# v7_mainboard_rpizerow.net
KiCad netlist of a schematic drawn in EAGLE
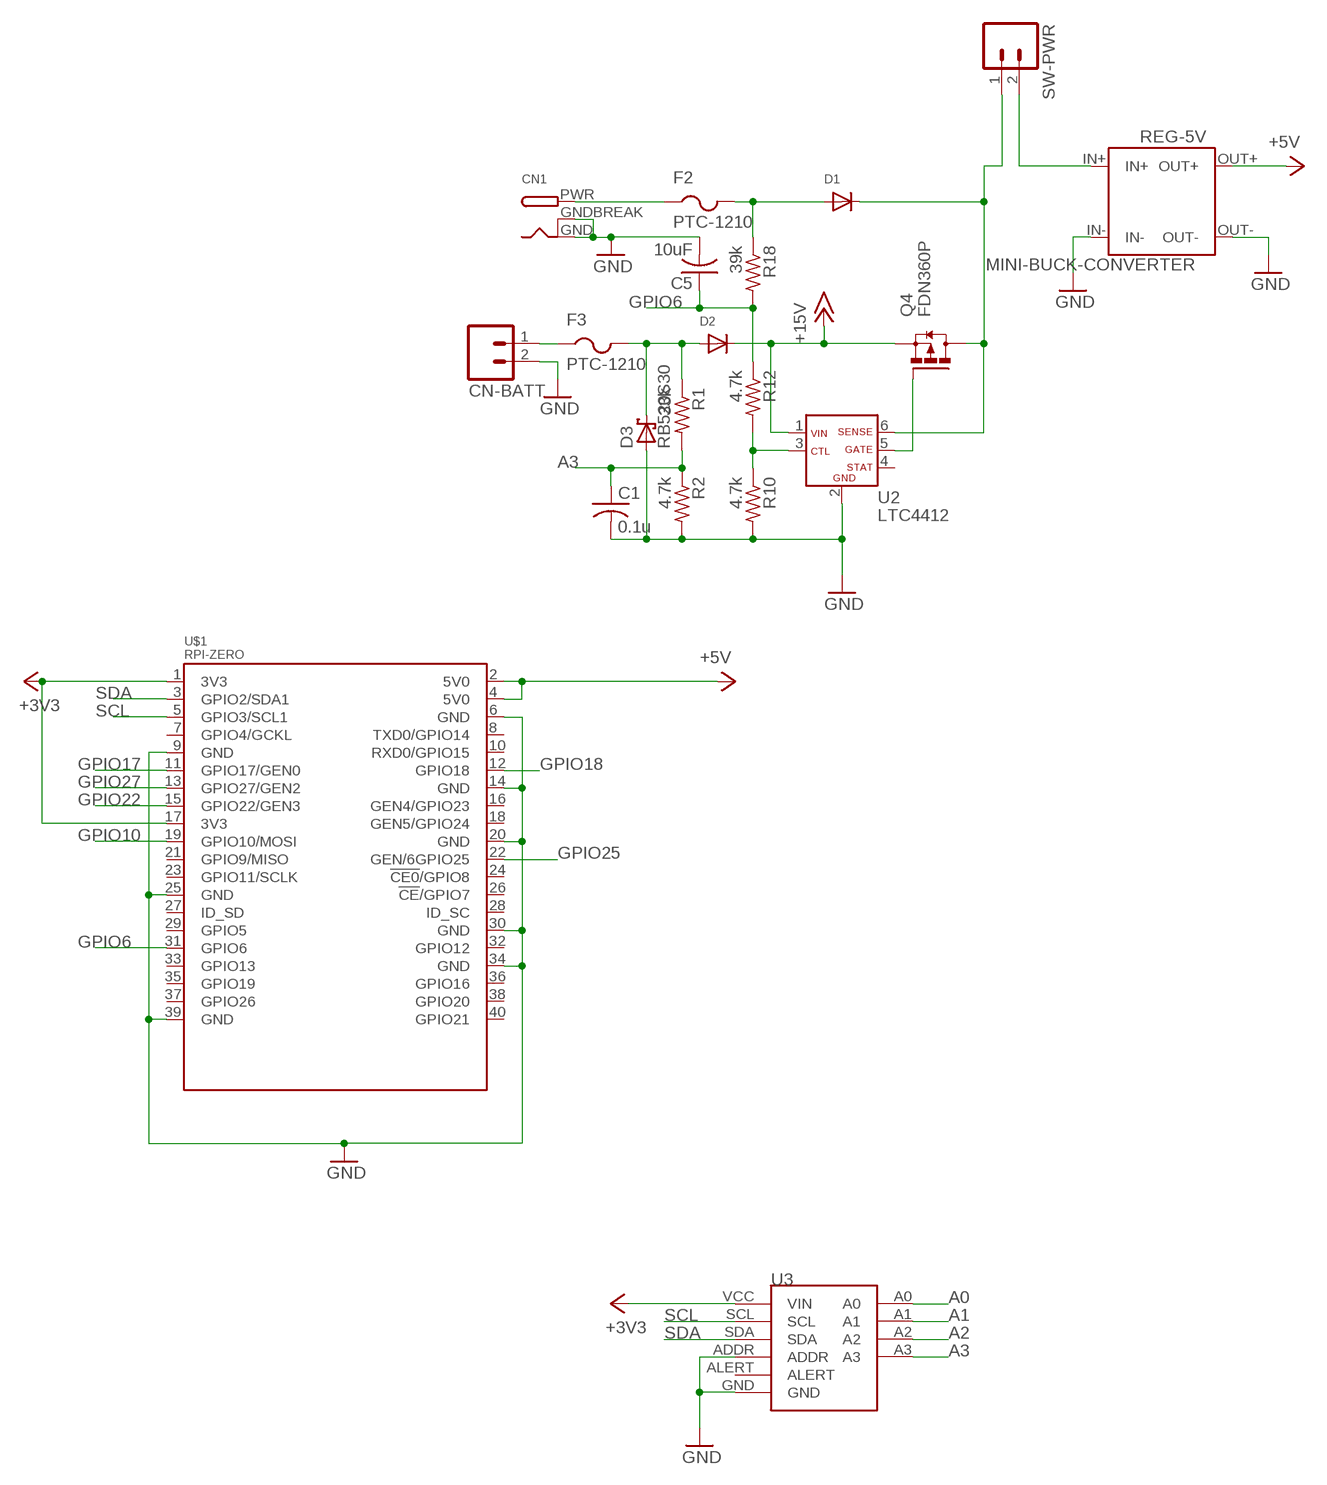
[diagram p0: schematic, sheet 1, part 1 of 2]
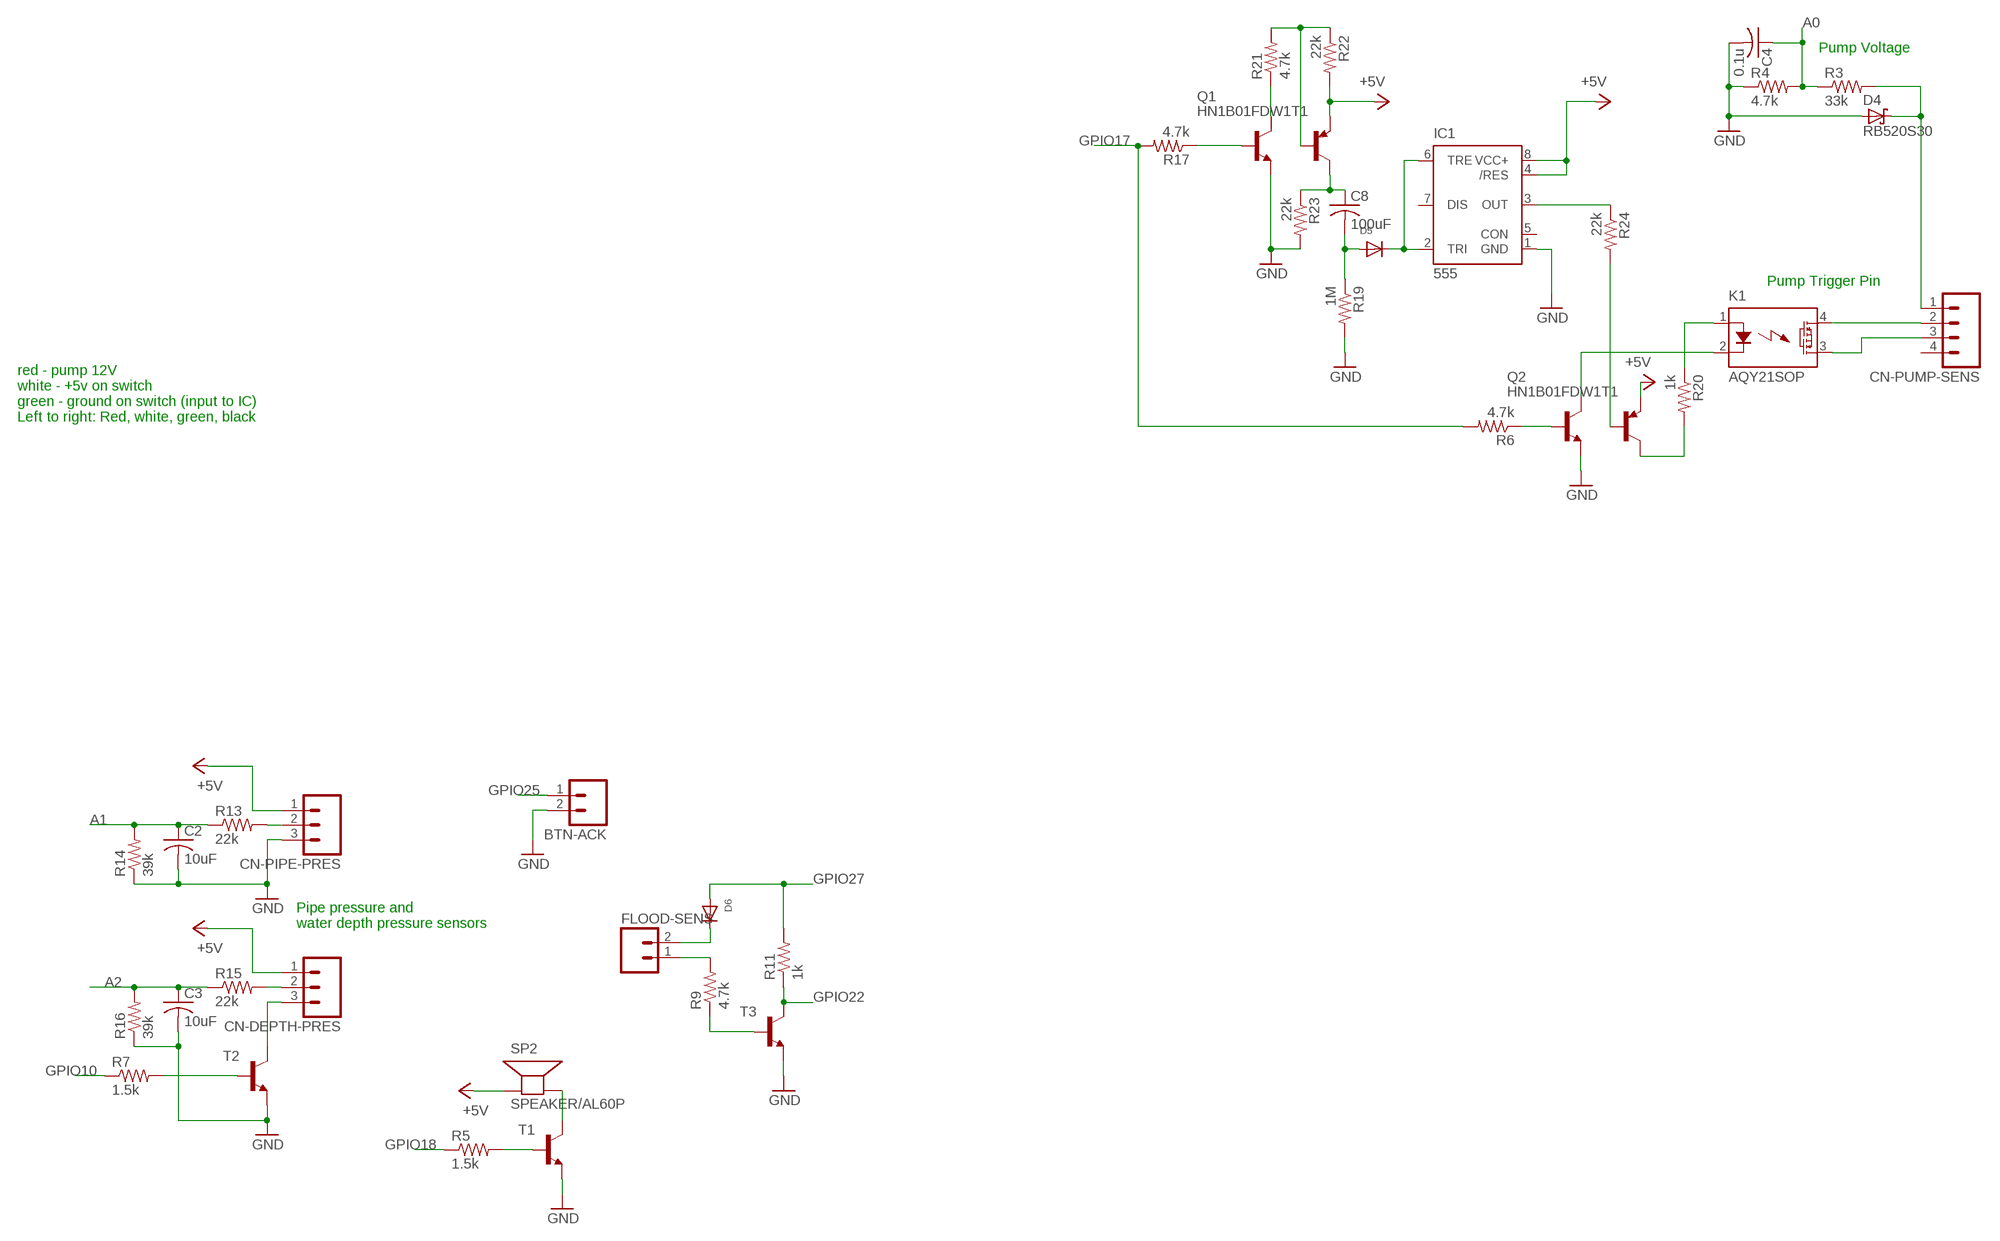
[diagram p1: schematic, sheet 1, part 2 of 2]

(export (version "E")
  (design (tool "Eeschema 10.0.6"))
  (components
    (comp (ref "BTN-ACK")
      (value "M02")
      (footprint "eagle-import:02P")
      (libsource (lib "eagle-import") (part "M02"))
    )
    (comp (ref "C1")
      (value "0.1u")
      (footprint "eagle-import:C0603K")
      (libsource (lib "eagle-import") (part "C-USC0603K"))
    )
    (comp (ref "C2")
      (value "10uF")
      (footprint "eagle-import:C0805K")
      (libsource (lib "eagle-import") (part "C-USC0805K"))
    )
    (comp (ref "C3")
      (value "10uF")
      (footprint "eagle-import:C0805K")
      (libsource (lib "eagle-import") (part "C-USC0805K"))
    )
    (comp (ref "C4")
      (value "0.1u")
      (footprint "eagle-import:C0603K")
      (libsource (lib "eagle-import") (part "C-USC0603K"))
    )
    (comp (ref "C5")
      (value "10uF")
      (footprint "eagle-import:C0805K")
      (libsource (lib "eagle-import") (part "C-USC0805K"))
    )
    (comp (ref "C8")
      (value "100uF")
      (footprint "eagle-import:C1210")
      (libsource (lib "eagle-import") (part "C-USC1210"))
    )
    (comp (ref "CN-BATT")
      (value "M02")
      (footprint "eagle-import:02P")
      (libsource (lib "eagle-import") (part "M02"))
    )
    (comp (ref "CN-DEPTH-PRES")
      (value "M03")
      (footprint "eagle-import:03P")
      (libsource (lib "eagle-import") (part "M03"))
    )
    (comp (ref "CN-PIPE-PRES")
      (value "M03")
      (footprint "eagle-import:03P")
      (libsource (lib "eagle-import") (part "M03"))
    )
    (comp (ref "CN-PUMP-SENS")
      (value "M04")
      (footprint "eagle-import:04P")
      (libsource (lib "eagle-import") (part "M04"))
    )
    (comp (ref "CN1")
      (value "DCBARRELPTH")
      (footprint "eagle-import:DCJACK_2MM_PTH")
      (libsource (lib "eagle-import") (part "DCBARRELPTH"))
    )
    (comp (ref "D1")
      (value "DIODESOD-323F")
      (footprint "eagle-import:SOD-323F")
      (libsource (lib "eagle-import") (part "DIODESOD-323F"))
    )
    (comp (ref "D2")
      (value "DIODESOD-323F")
      (footprint "eagle-import:SOD-323F")
      (libsource (lib "eagle-import") (part "DIODESOD-323F"))
    )
    (comp (ref "D3")
      (value "RB520S30")
      (footprint "eagle-import:SOD523")
      (libsource (lib "eagle-import") (part "RB520S30"))
    )
    (comp (ref "D4")
      (value "RB520S30")
      (footprint "eagle-import:SOD523")
      (libsource (lib "eagle-import") (part "RB520S30"))
    )
    (comp (ref "D5")
      (value "DIODESOD-323F")
      (footprint "eagle-import:SOD-323F")
      (libsource (lib "eagle-import") (part "DIODESOD-323F"))
    )
    (comp (ref "D6")
      (value "DIODESOD-323F")
      (footprint "eagle-import:SOD-323F")
      (libsource (lib "eagle-import") (part "DIODESOD-323F"))
    )
    (comp (ref "F2")
      (value "PTC-1210")
      (footprint "eagle-import:1210")
      (libsource (lib "eagle-import") (part "PTC-1210"))
    )
    (comp (ref "F3")
      (value "PTC-1210")
      (footprint "eagle-import:1210")
      (libsource (lib "eagle-import") (part "PTC-1210"))
    )
    (comp (ref "FLOOD-SENS")
      (value "M02")
      (footprint "eagle-import:02P")
      (libsource (lib "eagle-import") (part "M02"))
    )
    (comp (ref "IC1")
      (value "555")
      (footprint "eagle-import:SO08")
      (libsource (lib "eagle-import") (part "555D"))
    )
    (comp (ref "K1")
      (value "AQY21SOP")
      (footprint "eagle-import:SOP04")
      (libsource (lib "eagle-import") (part "AQYSOP21"))
    )
    (comp (ref "Q1")
      (value "HN1B01FDW1T1")
      (footprint "eagle-import:SOT23-6")
      (libsource (lib "eagle-import") (part "HN1B01FDW1T1"))
    )
    (comp (ref "Q2")
      (value "HN1B01FDW1T1")
      (footprint "eagle-import:SOT23-6")
      (libsource (lib "eagle-import") (part "HN1B01FDW1T1"))
    )
    (comp (ref "Q4")
      (value "FDN360P")
      (footprint "eagle-import:SUPER-SOT3")
      (libsource (lib "eagle-import") (part "FDN360P"))
    )
    (comp (ref "R1")
      (value "33k")
      (footprint "eagle-import:R0603")
      (libsource (lib "eagle-import") (part "R-US_R0603"))
    )
    (comp (ref "R2")
      (value "4.7k")
      (footprint "eagle-import:R0603")
      (libsource (lib "eagle-import") (part "R-US_R0603"))
    )
    (comp (ref "R3")
      (value "33k")
      (footprint "eagle-import:R0603")
      (libsource (lib "eagle-import") (part "R-US_R0603"))
    )
    (comp (ref "R4")
      (value "4.7k")
      (footprint "eagle-import:R0603")
      (libsource (lib "eagle-import") (part "R-US_R0603"))
    )
    (comp (ref "R5")
      (value "1.5k")
      (footprint "eagle-import:R0603")
      (libsource (lib "eagle-import") (part "R-US_R0603"))
    )
    (comp (ref "R6")
      (value "4.7k")
      (footprint "eagle-import:R0603")
      (libsource (lib "eagle-import") (part "R-US_R0603"))
    )
    (comp (ref "R7")
      (value "1.5k")
      (footprint "eagle-import:R0603")
      (libsource (lib "eagle-import") (part "R-US_R0603"))
    )
    (comp (ref "R9")
      (value "4.7k")
      (footprint "eagle-import:R0603")
      (libsource (lib "eagle-import") (part "R-US_R0603"))
    )
    (comp (ref "R10")
      (value "4.7k")
      (footprint "eagle-import:R0603")
      (libsource (lib "eagle-import") (part "R-US_R0603"))
    )
    (comp (ref "R11")
      (value "1k")
      (footprint "eagle-import:R0603")
      (libsource (lib "eagle-import") (part "R-US_R0603"))
    )
    (comp (ref "R12")
      (value "4.7k")
      (footprint "eagle-import:R0603")
      (libsource (lib "eagle-import") (part "R-US_R0603"))
    )
    (comp (ref "R13")
      (value "22k")
      (footprint "eagle-import:R0603")
      (libsource (lib "eagle-import") (part "R-US_R0603"))
    )
    (comp (ref "R14")
      (value "39k")
      (footprint "eagle-import:R0603")
      (libsource (lib "eagle-import") (part "R-US_R0603"))
    )
    (comp (ref "R15")
      (value "22k")
      (footprint "eagle-import:R0603")
      (libsource (lib "eagle-import") (part "R-US_R0603"))
    )
    (comp (ref "R16")
      (value "39k")
      (footprint "eagle-import:R0603")
      (libsource (lib "eagle-import") (part "R-US_R0603"))
    )
    (comp (ref "R17")
      (value "4.7k")
      (footprint "eagle-import:R0603")
      (libsource (lib "eagle-import") (part "R-US_R0603"))
    )
    (comp (ref "R18")
      (value "39k")
      (footprint "eagle-import:R0603")
      (libsource (lib "eagle-import") (part "R-US_R0603"))
    )
    (comp (ref "R19")
      (value "1M")
      (footprint "eagle-import:R0603")
      (libsource (lib "eagle-import") (part "R-US_R0603"))
    )
    (comp (ref "R20")
      (value "1k")
      (footprint "eagle-import:R0603")
      (libsource (lib "eagle-import") (part "R-US_R0603"))
    )
    (comp (ref "R21")
      (value "4.7k")
      (footprint "eagle-import:R0603")
      (libsource (lib "eagle-import") (part "R-US_R0603"))
    )
    (comp (ref "R22")
      (value "22k")
      (footprint "eagle-import:R0603")
      (libsource (lib "eagle-import") (part "R-US_R0603"))
    )
    (comp (ref "R23")
      (value "22k")
      (footprint "eagle-import:R0603")
      (libsource (lib "eagle-import") (part "R-US_R0603"))
    )
    (comp (ref "R24")
      (value "22k")
      (footprint "eagle-import:R0603")
      (libsource (lib "eagle-import") (part "R-US_R0603"))
    )
    (comp (ref "REG-5V")
      (value "MINI-BUCK-CONVERTER")
      (footprint "eagle-import:MINI-BUCK-CONVERTER")
      (libsource (lib "eagle-import") (part "MINI-BUCK-CONVERTER"))
    )
    (comp (ref "SP2")
      (value "SPEAKER/AL60P")
      (footprint "eagle-import:AL60P")
      (libsource (lib "eagle-import") (part "SPEAKER/AL60P"))
    )
    (comp (ref "SW-PWR")
      (value "M02")
      (footprint "eagle-import:02P")
      (libsource (lib "eagle-import") (part "M02"))
    )
    (comp (ref "T1")
      (value "BC808-NPN-SOT23-BEC")
      (footprint "eagle-import:SOT23-BEC")
      (libsource (lib "eagle-import") (part "-NPN-SOT23-BECBC808"))
    )
    (comp (ref "T2")
      (value "BC808-NPN-SOT23-BEC")
      (footprint "eagle-import:SOT23-BEC")
      (libsource (lib "eagle-import") (part "-NPN-SOT23-BECBC808"))
    )
    (comp (ref "T3")
      (value "BC808-NPN-SOT23-BEC")
      (footprint "eagle-import:SOT23-BEC")
      (libsource (lib "eagle-import") (part "-NPN-SOT23-BECBC808"))
    )
    (comp (ref "U$1")
      (value "RPI-ZERO")
      (footprint "eagle-import:RASPBERRYPI_BASTELSTUBE_V13_RASPI_BOARD_B+_FULL")
      (libsource (lib "eagle-import") (part "RPI-ZERO"))
    )
    (comp (ref "U2")
      (value "LTC4412")
      (footprint "eagle-import:SOT23-6")
      (libsource (lib "eagle-import") (part "LTC4412"))
    )
    (comp (ref "U3")
      (value "GY-ADS1115THM")
      (footprint "eagle-import:GY-ADS1115-THM")
      (libsource (lib "eagle-import") (part "GY-ADS1115THM"))
    )
  )
  (nets
    (net (code "1") (name "+3V3") (class "Default")
      (node (ref "U$1") (pin "1") (pinfunction "3V3_1") (pintype "power_in"))
      (node (ref "U$1") (pin "17") (pinfunction "3V3_17") (pintype "power_in"))
      (node (ref "U3") (pin "VCC") (pinfunction "VIN_VCC") (pintype "bidirectional"))
    )
    (net (code "2") (name "+5V") (class "Default")
      (node (ref "CN-DEPTH-PRES") (pin "1") (pinfunction "1_1") (pintype "passive"))
      (node (ref "CN-PIPE-PRES") (pin "1") (pinfunction "1_1") (pintype "passive"))
      (node (ref "IC1") (pin "4") (pinfunction "/RES_4") (pintype "input"))
      (node (ref "IC1") (pin "8") (pinfunction "VCC+_8") (pintype "power_in"))
      (node (ref "Q1") (pin "1") (pinfunction "PNP-E_1") (pintype "passive"))
      (node (ref "Q2") (pin "1") (pinfunction "PNP-E_1") (pintype "passive"))
      (node (ref "R22") (pin "2") (pinfunction "2_2") (pintype "passive"))
      (node (ref "REG-5V") (pin "OUT+") (pinfunction "OUT+_OUT+") (pintype "power_in"))
      (node (ref "SP2") (pin "1") (pinfunction "+_1") (pintype "passive"))
      (node (ref "U$1") (pin "2") (pinfunction "5V0_2") (pintype "power_in"))
      (node (ref "U$1") (pin "4") (pinfunction "5V0_4") (pintype "power_in"))
    )
    (net (code "3") (name "+15V") (class "Default")
      (node (ref "D2") (pin "C") (pinfunction "C_C") (pintype "passive"))
      (node (ref "Q4") (pin "2") (pinfunction "S_2") (pintype "passive"))
      (node (ref "U2") (pin "1") (pinfunction "VIN_1") (pintype "power_in"))
    )
    (net (code "4") (name "/A0") (class "Default")
      (node (ref "C4") (pin "1") (pinfunction "1_1") (pintype "passive"))
      (node (ref "R3") (pin "1") (pinfunction "1_1") (pintype "passive"))
      (node (ref "R4") (pin "2") (pinfunction "2_2") (pintype "passive"))
      (node (ref "U3") (pin "A0") (pinfunction "A0_A0") (pintype "bidirectional"))
    )
    (net (code "5") (name "/A1") (class "Default")
      (node (ref "C2") (pin "1") (pinfunction "1_1") (pintype "passive"))
      (node (ref "R13") (pin "1") (pinfunction "1_1") (pintype "passive"))
      (node (ref "R14") (pin "2") (pinfunction "2_2") (pintype "passive"))
      (node (ref "U3") (pin "A1") (pinfunction "A1_A1") (pintype "bidirectional"))
    )
    (net (code "6") (name "/A2") (class "Default")
      (node (ref "C3") (pin "1") (pinfunction "1_1") (pintype "passive"))
      (node (ref "R15") (pin "1") (pinfunction "1_1") (pintype "passive"))
      (node (ref "R16") (pin "2") (pinfunction "2_2") (pintype "passive"))
      (node (ref "U3") (pin "A2") (pinfunction "A2_A2") (pintype "bidirectional"))
    )
    (net (code "7") (name "/A3") (class "Default")
      (node (ref "C1") (pin "1") (pinfunction "1_1") (pintype "passive"))
      (node (ref "R1") (pin "2") (pinfunction "2_2") (pintype "passive"))
      (node (ref "R2") (pin "1") (pinfunction "1_1") (pintype "passive"))
      (node (ref "U3") (pin "A3") (pinfunction "A3_A3") (pintype "bidirectional"))
    )
    (net (code "8") (name "/GPIO6") (class "Default")
      (node (ref "C5") (pin "1") (pinfunction "1_1") (pintype "passive"))
      (node (ref "R12") (pin "1") (pinfunction "1_1") (pintype "passive"))
      (node (ref "R18") (pin "2") (pinfunction "2_2") (pintype "passive"))
      (node (ref "U$1") (pin "31") (pinfunction "GPIO6_31") (pintype "bidirectional"))
    )
    (net (code "9") (name "/GPIO10") (class "Default")
      (node (ref "R7") (pin "1") (pinfunction "1_1") (pintype "passive"))
      (node (ref "U$1") (pin "19") (pinfunction "GPIO10/MOSI_19") (pintype "bidirectional"))
    )
    (net (code "10") (name "/GPIO17") (class "Default")
      (node (ref "R17") (pin "2") (pinfunction "2_2") (pintype "passive"))
      (node (ref "R6") (pin "2") (pinfunction "2_2") (pintype "passive"))
      (node (ref "U$1") (pin "11") (pinfunction "GPIO17/GEN0_11") (pintype "bidirectional"))
    )
    (net (code "11") (name "/GPIO18") (class "Default")
      (node (ref "R5") (pin "1") (pinfunction "1_1") (pintype "passive"))
      (node (ref "U$1") (pin "12") (pinfunction "GPIO18_12") (pintype "bidirectional"))
    )
    (net (code "12") (name "/GPIO22") (class "Default")
      (node (ref "R11") (pin "1") (pinfunction "1_1") (pintype "passive"))
      (node (ref "T3") (pin "C") (pinfunction "C_C") (pintype "passive"))
      (node (ref "U$1") (pin "15") (pinfunction "GPIO22/GEN3_15") (pintype "bidirectional"))
    )
    (net (code "13") (name "/GPIO25") (class "Default")
      (node (ref "BTN-ACK") (pin "1") (pinfunction "1_1") (pintype "passive"))
      (node (ref "U$1") (pin "22") (pinfunction "GEN/6GPIO25_22") (pintype "bidirectional"))
    )
    (net (code "14") (name "/GPIO27") (class "Default")
      (node (ref "D6") (pin "A") (pinfunction "A_A") (pintype "passive"))
      (node (ref "R11") (pin "2") (pinfunction "2_2") (pintype "passive"))
      (node (ref "U$1") (pin "13") (pinfunction "GPIO27/GEN2_13") (pintype "bidirectional"))
    )
    (net (code "15") (name "/SCL") (class "Default")
      (node (ref "U$1") (pin "5") (pinfunction "GPIO3/SCL1_5") (pintype "bidirectional"))
      (node (ref "U3") (pin "SCL") (pinfunction "SCL_SCL") (pintype "bidirectional"))
    )
    (net (code "16") (name "/SDA") (class "Default")
      (node (ref "U$1") (pin "3") (pinfunction "GPIO2/SDA1_3") (pintype "bidirectional"))
      (node (ref "U3") (pin "SDA") (pinfunction "SDA_SDA") (pintype "bidirectional"))
    )
    (net (code "17") (name "GND") (class "Default")
      (node (ref "BTN-ACK") (pin "2") (pinfunction "2_2") (pintype "passive"))
      (node (ref "C1") (pin "2") (pinfunction "2_2") (pintype "passive"))
      (node (ref "C2") (pin "2") (pinfunction "2_2") (pintype "passive"))
      (node (ref "C3") (pin "2") (pinfunction "2_2") (pintype "passive"))
      (node (ref "C4") (pin "2") (pinfunction "2_2") (pintype "passive"))
      (node (ref "C5") (pin "2") (pinfunction "2_2") (pintype "passive"))
      (node (ref "CN-BATT") (pin "2") (pinfunction "2_2") (pintype "passive"))
      (node (ref "CN-PIPE-PRES") (pin "3") (pinfunction "3_3") (pintype "passive"))
      (node (ref "CN1") (pin "GND") (pinfunction "GND_GND") (pintype "power_in"))
      (node (ref "CN1") (pin "GNDBREAK") (pinfunction "GNDBREAK_GNDBREAK") (pintype "power_in"))
      (node (ref "D3") (pin "2") (pinfunction "A_2") (pintype "passive"))
      (node (ref "D4") (pin "2") (pinfunction "A_2") (pintype "passive"))
      (node (ref "IC1") (pin "1") (pinfunction "GND_1") (pintype "power_in"))
      (node (ref "Q1") (pin "4") (pinfunction "NPN-E_4") (pintype "passive"))
      (node (ref "Q2") (pin "4") (pinfunction "NPN-E_4") (pintype "passive"))
      (node (ref "R10") (pin "2") (pinfunction "2_2") (pintype "passive"))
      (node (ref "R14") (pin "1") (pinfunction "1_1") (pintype "passive"))
      (node (ref "R16") (pin "1") (pinfunction "1_1") (pintype "passive"))
      (node (ref "R19") (pin "2") (pinfunction "2_2") (pintype "passive"))
      (node (ref "R2") (pin "2") (pinfunction "2_2") (pintype "passive"))
      (node (ref "R23") (pin "2") (pinfunction "2_2") (pintype "passive"))
      (node (ref "R4") (pin "1") (pinfunction "1_1") (pintype "passive"))
      (node (ref "REG-5V") (pin "IN-") (pinfunction "IN-_IN-") (pintype "power_in"))
      (node (ref "REG-5V") (pin "OUT-") (pinfunction "OUT-_OUT-") (pintype "power_in"))
      (node (ref "T1") (pin "E") (pinfunction "E_E") (pintype "passive"))
      (node (ref "T2") (pin "E") (pinfunction "E_E") (pintype "passive"))
      (node (ref "T3") (pin "E") (pinfunction "E_E") (pintype "passive"))
      (node (ref "U$1") (pin "14") (pinfunction "GND_14") (pintype "power_in"))
      (node (ref "U$1") (pin "20") (pinfunction "GND_20") (pintype "power_in"))
      (node (ref "U$1") (pin "25") (pinfunction "GND_25") (pintype "power_in"))
      (node (ref "U$1") (pin "30") (pinfunction "GND_30") (pintype "power_in"))
      (node (ref "U$1") (pin "34") (pinfunction "GND_34") (pintype "power_in"))
      (node (ref "U$1") (pin "39") (pinfunction "GND_39") (pintype "power_in"))
      (node (ref "U$1") (pin "6") (pinfunction "GND_6") (pintype "power_in"))
      (node (ref "U$1") (pin "9") (pinfunction "GND_9") (pintype "power_in"))
      (node (ref "U2") (pin "2") (pinfunction "GND_2") (pintype "power_in"))
      (node (ref "U3") (pin "ADDR") (pinfunction "ADDR_ADDR") (pintype "bidirectional"))
      (node (ref "U3") (pin "GND") (pinfunction "GND_GND") (pintype "bidirectional"))
    )
    (net (code "18") (name "Net-(C8-Pad2)") (class "Default")
      (node (ref "C8") (pin "2") (pinfunction "2_2") (pintype "passive"))
      (node (ref "D5") (pin "A") (pinfunction "A_A") (pintype "passive"))
      (node (ref "R19") (pin "1") (pinfunction "1_1") (pintype "passive"))
    )
    (net (code "19") (name "Net-(CN-BATT-Pad1)") (class "Default")
      (node (ref "CN-BATT") (pin "1") (pinfunction "1_1") (pintype "passive"))
      (node (ref "F3") (pin "1") (pinfunction "1_1") (pintype "passive"))
    )
    (net (code "20") (name "Net-(CN-DEPTH-PRES-Pad2)") (class "Default")
      (node (ref "CN-DEPTH-PRES") (pin "2") (pinfunction "2_2") (pintype "passive"))
      (node (ref "R15") (pin "2") (pinfunction "2_2") (pintype "passive"))
    )
    (net (code "21") (name "Net-(CN-DEPTH-PRES-Pad3)") (class "Default")
      (node (ref "CN-DEPTH-PRES") (pin "3") (pinfunction "3_3") (pintype "passive"))
      (node (ref "T2") (pin "C") (pinfunction "C_C") (pintype "passive"))
    )
    (net (code "22") (name "Net-(CN-PIPE-PRES-Pad2)") (class "Default")
      (node (ref "CN-PIPE-PRES") (pin "2") (pinfunction "2_2") (pintype "passive"))
      (node (ref "R13") (pin "2") (pinfunction "2_2") (pintype "passive"))
    )
    (net (code "23") (name "Net-(CN1-PadPWR)") (class "Default")
      (node (ref "CN1") (pin "PWR") (pinfunction "PWR_PWR") (pintype "power_in"))
      (node (ref "F2") (pin "1") (pinfunction "1_1") (pintype "passive"))
    )
    (net (code "24") (name "Net-(D1-PadA)") (class "Default")
      (node (ref "D1") (pin "A") (pinfunction "A_A") (pintype "passive"))
      (node (ref "F2") (pin "2") (pinfunction "2_2") (pintype "passive"))
      (node (ref "R18") (pin "1") (pinfunction "1_1") (pintype "passive"))
    )
    (net (code "25") (name "Net-(D3-K)") (class "Default")
      (node (ref "D2") (pin "A") (pinfunction "A_A") (pintype "passive"))
      (node (ref "D3") (pin "1") (pinfunction "K_1") (pintype "passive"))
      (node (ref "F3") (pin "2") (pinfunction "2_2") (pintype "passive"))
      (node (ref "R1") (pin "1") (pinfunction "1_1") (pintype "passive"))
    )
    (net (code "26") (name "Net-(D4-K)") (class "Default")
      (node (ref "CN-PUMP-SENS") (pin "1") (pinfunction "1_1") (pintype "passive"))
      (node (ref "D4") (pin "1") (pinfunction "K_1") (pintype "passive"))
      (node (ref "R3") (pin "2") (pinfunction "2_2") (pintype "passive"))
    )
    (net (code "27") (name "Net-(D6-PadC)") (class "Default")
      (node (ref "D6") (pin "C") (pinfunction "C_C") (pintype "passive"))
      (node (ref "FLOOD-SENS") (pin "2") (pinfunction "2_2") (pintype "passive"))
    )
    (net (code "28") (name "Net-(FLOOD-SENS-Pad1)") (class "Default")
      (node (ref "FLOOD-SENS") (pin "1") (pinfunction "1_1") (pintype "passive"))
      (node (ref "R9") (pin "2") (pinfunction "2_2") (pintype "passive"))
    )
    (net (code "29") (name "Net-(IC1-OUT)") (class "Default")
      (node (ref "IC1") (pin "3") (pinfunction "OUT_3") (pintype "output"))
      (node (ref "R24") (pin "1") (pinfunction "1_1") (pintype "passive"))
    )
    (net (code "30") (name "Net-(IC1-TRE)") (class "Default")
      (node (ref "D5") (pin "C") (pinfunction "C_C") (pintype "passive"))
      (node (ref "IC1") (pin "2") (pinfunction "TRI_2") (pintype "input"))
      (node (ref "IC1") (pin "6") (pinfunction "TRE_6") (pintype "input"))
    )
    (net (code "31") (name "Net-(K1-A)") (class "Default")
      (node (ref "K1") (pin "1") (pinfunction "A_1") (pintype "passive"))
      (node (ref "R20") (pin "1") (pinfunction "1_1") (pintype "passive"))
    )
    (net (code "32") (name "Net-(K1-DS1)") (class "Default")
      (node (ref "CN-PUMP-SENS") (pin "2") (pinfunction "2_2") (pintype "passive"))
      (node (ref "K1") (pin "4") (pinfunction "DS1_4") (pintype "passive"))
    )
    (net (code "33") (name "Net-(K1-DS2)") (class "Default")
      (node (ref "CN-PUMP-SENS") (pin "3") (pinfunction "3_3") (pintype "passive"))
      (node (ref "K1") (pin "3") (pinfunction "DS2_3") (pintype "passive"))
    )
    (net (code "34") (name "Net-(K1-K)") (class "Default")
      (node (ref "K1") (pin "2") (pinfunction "K_2") (pintype "passive"))
      (node (ref "Q2") (pin "3") (pinfunction "NPN-C_3") (pintype "passive"))
    )
    (net (code "35") (name "Net-(Q1-NPN-B)") (class "Default")
      (node (ref "Q1") (pin "5") (pinfunction "NPN-B_5") (pintype "passive"))
      (node (ref "R17") (pin "1") (pinfunction "1_1") (pintype "passive"))
    )
    (net (code "36") (name "Net-(Q1-NPN-C)") (class "Default")
      (node (ref "Q1") (pin "3") (pinfunction "NPN-C_3") (pintype "passive"))
      (node (ref "R21") (pin "1") (pinfunction "1_1") (pintype "passive"))
    )
    (net (code "37") (name "Net-(Q1-PNP-B)") (class "Default")
      (node (ref "Q1") (pin "2") (pinfunction "PNP-B_2") (pintype "passive"))
      (node (ref "R21") (pin "2") (pinfunction "2_2") (pintype "passive"))
      (node (ref "R22") (pin "1") (pinfunction "1_1") (pintype "passive"))
    )
    (net (code "38") (name "Net-(Q1-PNP-C)") (class "Default")
      (node (ref "C8") (pin "1") (pinfunction "1_1") (pintype "passive"))
      (node (ref "Q1") (pin "6") (pinfunction "PNP-C_6") (pintype "passive"))
      (node (ref "R23") (pin "1") (pinfunction "1_1") (pintype "passive"))
    )
    (net (code "39") (name "Net-(Q2-NPN-B)") (class "Default")
      (node (ref "Q2") (pin "5") (pinfunction "NPN-B_5") (pintype "passive"))
      (node (ref "R6") (pin "1") (pinfunction "1_1") (pintype "passive"))
    )
    (net (code "40") (name "Net-(Q2-PNP-B)") (class "Default")
      (node (ref "Q2") (pin "2") (pinfunction "PNP-B_2") (pintype "passive"))
      (node (ref "R24") (pin "2") (pinfunction "2_2") (pintype "passive"))
    )
    (net (code "41") (name "Net-(Q2-PNP-C)") (class "Default")
      (node (ref "Q2") (pin "6") (pinfunction "PNP-C_6") (pintype "passive"))
      (node (ref "R20") (pin "2") (pinfunction "2_2") (pintype "passive"))
    )
    (net (code "42") (name "Net-(Q4-D)") (class "Default")
      (node (ref "D1") (pin "C") (pinfunction "C_C") (pintype "passive"))
      (node (ref "Q4") (pin "3") (pinfunction "D_3") (pintype "passive"))
      (node (ref "SW-PWR") (pin "1") (pinfunction "1_1") (pintype "passive"))
      (node (ref "U2") (pin "6") (pinfunction "SENSE_6") (pintype "input"))
    )
    (net (code "43") (name "Net-(Q4-G)") (class "Default")
      (node (ref "Q4") (pin "1") (pinfunction "G_1") (pintype "passive"))
      (node (ref "U2") (pin "5") (pinfunction "GATE_5") (pintype "output"))
    )
    (net (code "44") (name "Net-(R5-Pad2)") (class "Default")
      (node (ref "R5") (pin "2") (pinfunction "2_2") (pintype "passive"))
      (node (ref "T1") (pin "B") (pinfunction "B_B") (pintype "passive"))
    )
    (net (code "45") (name "Net-(R7-Pad2)") (class "Default")
      (node (ref "R7") (pin "2") (pinfunction "2_2") (pintype "passive"))
      (node (ref "T2") (pin "B") (pinfunction "B_B") (pintype "passive"))
    )
    (net (code "46") (name "Net-(R9-Pad1)") (class "Default")
      (node (ref "R9") (pin "1") (pinfunction "1_1") (pintype "passive"))
      (node (ref "T3") (pin "B") (pinfunction "B_B") (pintype "passive"))
    )
    (net (code "47") (name "Net-(REG-5V-PadIN+)") (class "Default")
      (node (ref "REG-5V") (pin "IN+") (pinfunction "IN+_IN+") (pintype "power_in"))
      (node (ref "SW-PWR") (pin "2") (pinfunction "2_2") (pintype "passive"))
    )
    (net (code "48") (name "Net-(SP2--)") (class "Default")
      (node (ref "SP2") (pin "2") (pinfunction "-_2") (pintype "passive"))
      (node (ref "T1") (pin "C") (pinfunction "C_C") (pintype "passive"))
    )
    (net (code "49") (name "Net-(U2-CTL)") (class "Default")
      (node (ref "R10") (pin "1") (pinfunction "1_1") (pintype "passive"))
      (node (ref "R12") (pin "2") (pinfunction "2_2") (pintype "passive"))
      (node (ref "U2") (pin "3") (pinfunction "CTL_3") (pintype "input"))
    )
    (net (code "50") (name "unconnected-(CN-PUMP-SENS-Pad4)") (class "Default")
      (node (ref "CN-PUMP-SENS") (pin "4") (pinfunction "4_4") (pintype "passive"))
    )
    (net (code "51") (name "unconnected-(IC1-CON-Pad5)") (class "Default")
      (node (ref "IC1") (pin "5") (pinfunction "CON_5") (pintype "input"))
    )
    (net (code "52") (name "unconnected-(IC1-DIS-Pad7)") (class "Default")
      (node (ref "IC1") (pin "7") (pinfunction "DIS_7") (pintype "input"))
    )
    (net (code "53") (name "unconnected-(U$1-GEN4{slash}GPIO23-Pad16)") (class "Default")
      (node (ref "U$1") (pin "16") (pinfunction "GEN4/GPIO23_16") (pintype "bidirectional"))
    )
    (net (code "54") (name "unconnected-(U$1-GEN5{slash}GPIO24-Pad18)") (class "Default")
      (node (ref "U$1") (pin "18") (pinfunction "GEN5/GPIO24_18") (pintype "bidirectional"))
    )
    (net (code "55") (name "unconnected-(U$1-GPIO4{slash}GCKL-Pad7)") (class "Default")
      (node (ref "U$1") (pin "7") (pinfunction "GPIO4/GCKL_7") (pintype "bidirectional"))
    )
    (net (code "56") (name "unconnected-(U$1-GPIO5-Pad29)") (class "Default")
      (node (ref "U$1") (pin "29") (pinfunction "GPIO5_29") (pintype "bidirectional"))
    )
    (net (code "57") (name "unconnected-(U$1-GPIO9{slash}MISO-Pad21)") (class "Default")
      (node (ref "U$1") (pin "21") (pinfunction "GPIO9/MISO_21") (pintype "bidirectional"))
    )
    (net (code "58") (name "unconnected-(U$1-GPIO11{slash}SCLK-Pad23)") (class "Default")
      (node (ref "U$1") (pin "23") (pinfunction "GPIO11/SCLK_23") (pintype "bidirectional"))
    )
    (net (code "59") (name "unconnected-(U$1-GPIO12-Pad32)") (class "Default")
      (node (ref "U$1") (pin "32") (pinfunction "GPIO12_32") (pintype "bidirectional"))
    )
    (net (code "60") (name "unconnected-(U$1-GPIO13-Pad33)") (class "Default")
      (node (ref "U$1") (pin "33") (pinfunction "GPIO13_33") (pintype "bidirectional"))
    )
    (net (code "61") (name "unconnected-(U$1-GPIO16-Pad36)") (class "Default")
      (node (ref "U$1") (pin "36") (pinfunction "GPIO16_36") (pintype "bidirectional"))
    )
    (net (code "62") (name "unconnected-(U$1-GPIO19-Pad35)") (class "Default")
      (node (ref "U$1") (pin "35") (pinfunction "GPIO19_35") (pintype "bidirectional"))
    )
    (net (code "63") (name "unconnected-(U$1-GPIO20-Pad38)") (class "Default")
      (node (ref "U$1") (pin "38") (pinfunction "GPIO20_38") (pintype "bidirectional"))
    )
    (net (code "64") (name "unconnected-(U$1-GPIO21-Pad40)") (class "Default")
      (node (ref "U$1") (pin "40") (pinfunction "GPIO21_40") (pintype "bidirectional"))
    )
    (net (code "65") (name "unconnected-(U$1-GPIO26-Pad37)") (class "Default")
      (node (ref "U$1") (pin "37") (pinfunction "GPIO26_37") (pintype "bidirectional"))
    )
    (net (code "66") (name "unconnected-(U$1-ID_SC-Pad28)") (class "Default")
      (node (ref "U$1") (pin "28") (pinfunction "ID_SC_28") (pintype "bidirectional"))
    )
    (net (code "67") (name "unconnected-(U$1-ID_SD-Pad27)") (class "Default")
      (node (ref "U$1") (pin "27") (pinfunction "ID_SD_27") (pintype "bidirectional"))
    )
    (net (code "68") (name "unconnected-(U$1-RXD0{slash}GPIO15-Pad10)") (class "Default")
      (node (ref "U$1") (pin "10") (pinfunction "RXD0/GPIO15_10") (pintype "bidirectional"))
    )
    (net (code "69") (name "unconnected-(U$1-TXD0{slash}GPIO14-Pad8)") (class "Default")
      (node (ref "U$1") (pin "8") (pinfunction "TXD0/GPIO14_8") (pintype "bidirectional"))
    )
    (net (code "70") (name "unconnected-(U$1-~{CE0}{slash}GPIO8-Pad24)") (class "Default")
      (node (ref "U$1") (pin "24") (pinfunction "~{CE0}/GPIO8_24") (pintype "bidirectional"))
    )
    (net (code "71") (name "unconnected-(U$1-~{CE}{slash}GPIO7-Pad26)") (class "Default")
      (node (ref "U$1") (pin "26") (pinfunction "~{CE}/GPIO7_26") (pintype "bidirectional"))
    )
    (net (code "72") (name "unconnected-(U2-STAT-Pad4)") (class "Default")
      (node (ref "U2") (pin "4") (pinfunction "STAT_4") (pintype "open_collector"))
    )
    (net (code "73") (name "unconnected-(U3-PadALERT)") (class "Default")
      (node (ref "U3") (pin "ALERT") (pinfunction "ALERT_ALERT") (pintype "bidirectional"))
    )
  )
)
